# Schematic.net
KiCad netlist of a schematic drawn in Altium Designer
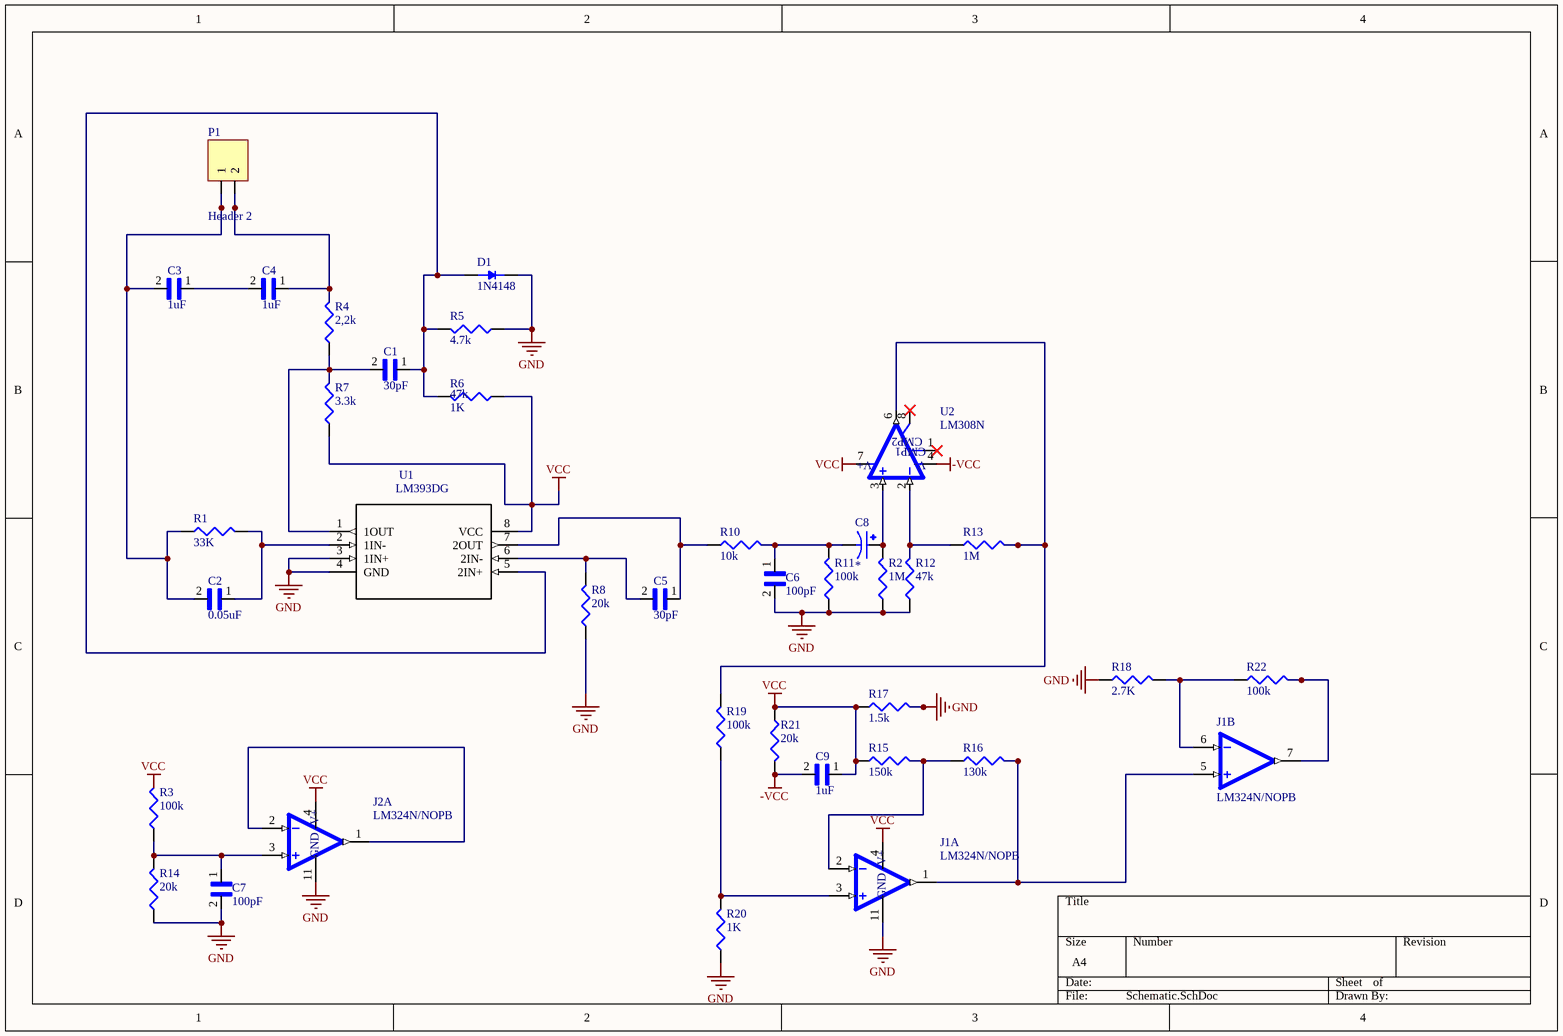
[diagram p0: Schematic.SchDoc]

(export (version "E")
  (design (tool "Eeschema 10.0.6"))
  (components
    (comp (ref "C1")
      (value "30pF")
      (footprint "CAPC3216X190")
      (description "ÐšÐµÑ€Ð°Ð¼Ð¸Ñ‡ÐµÑÐºÐ¸Ð¹ ÐºÐ¾Ð½Ð´ÐµÐ½ÑÐ°Ñ‚Ð¾Ñ€")
      (fields (field (name "MP") "GRM31CC80E157ME11K") (field (name "MF") "Murata"))
      (libsource (lib "GRM31CC80E157ME11K") (part "GRM31CC80E157ME11K"))
    )
    (comp (ref "C2")
      (value "0.05uF")
      (footprint "CAPC3216X190")
      (description "ÐšÐµÑ€Ð°Ð¼Ð¸Ñ‡ÐµÑÐºÐ¸Ð¹ ÐºÐ¾Ð½Ð´ÐµÐ½ÑÐ°Ñ‚Ð¾Ñ€")
      (fields (field (name "MP") "GRM31CC80E157ME11K") (field (name "MF") "Murata"))
      (libsource (lib "GRM31CC80E157ME11K") (part "GRM31CC80E157ME11K"))
    )
    (comp (ref "C3")
      (value "1uF")
      (footprint "CAPC3216X190")
      (description "ÐšÐµÑ€Ð°Ð¼Ð¸Ñ‡ÐµÑÐºÐ¸Ð¹ ÐºÐ¾Ð½Ð´ÐµÐ½ÑÐ°Ñ‚Ð¾Ñ€")
      (fields (field (name "MP") "GRM31CC80E157ME11K") (field (name "MF") "Murata"))
      (libsource (lib "GRM31CC80E157ME11K") (part "GRM31CC80E157ME11K"))
    )
    (comp (ref "C4")
      (value "1uF")
      (footprint "CAPC3216X190")
      (description "ÐšÐµÑ€Ð°Ð¼Ð¸Ñ‡ÐµÑÐºÐ¸Ð¹ ÐºÐ¾Ð½Ð´ÐµÐ½ÑÐ°Ñ‚Ð¾Ñ€")
      (fields (field (name "MP") "GRM31CC80E157ME11K") (field (name "MF") "Murata"))
      (libsource (lib "GRM31CC80E157ME11K") (part "GRM31CC80E157ME11K"))
    )
    (comp (ref "C5")
      (value "30pF")
      (footprint "CAPC3216X190")
      (description "ÐšÐµÑ€Ð°Ð¼Ð¸Ñ‡ÐµÑÐºÐ¸Ð¹ ÐºÐ¾Ð½Ð´ÐµÐ½ÑÐ°Ñ‚Ð¾Ñ€")
      (fields (field (name "MP") "GRM31CC80E157ME11K") (field (name "MF") "Murata"))
      (libsource (lib "GRM31CC80E157ME11K") (part "GRM31CC80E157ME11K"))
    )
    (comp (ref "C6")
      (value "100pF")
      (footprint "CAPC3216X190")
      (description "ÐšÐµÑ€Ð°Ð¼Ð¸Ñ‡ÐµÑÐºÐ¸Ð¹ ÐºÐ¾Ð½Ð´ÐµÐ½ÑÐ°Ñ‚Ð¾Ñ€")
      (fields (field (name "MP") "GRM31CC80E157ME11K") (field (name "MF") "Murata"))
      (libsource (lib "") (part "GRM31CC80E157ME11K_1"))
    )
    (comp (ref "C7")
      (value "100pF")
      (footprint "CAPC3216X190")
      (description "ÐšÐµÑ€Ð°Ð¼Ð¸Ñ‡ÐµÑÐºÐ¸Ð¹ ÐºÐ¾Ð½Ð´ÐµÐ½ÑÐ°Ñ‚Ð¾Ñ€")
      (fields (field (name "MP") "GRM31CC80E157ME11K") (field (name "MF") "Murata"))
      (libsource (lib "") (part "GRM31CC80E157ME11K_1"))
    )
    (comp (ref "C8")
      (value "*")
      (footprint "CAPPRD250W50D630H1120")
      (description "CAP ALUM 33UF 20% 63V RADIAL")
      (fields (field (name "MF") "Panasonic") (field (name "MP") "ECA1JM330I"))
      (libsource (lib "ECA1JM330I") (part "ECA1JM330I"))
    )
    (comp (ref "C9")
      (value "1uF")
      (footprint "CAPC3216X190")
      (description "ÐšÐµÑ€Ð°Ð¼Ð¸Ñ‡ÐµÑÐºÐ¸Ð¹ ÐºÐ¾Ð½Ð´ÐµÐ½ÑÐ°Ñ‚Ð¾Ñ€")
      (fields (field (name "MP") "GRM31CC80E157ME11K") (field (name "MF") "Murata"))
      (libsource (lib "GRM31CC80E157ME11K") (part "GRM31CC80E157ME11K"))
    )
    (comp (ref "D1")
      (value "1N4148")
      (footprint "DIODFN60X30X36-2N")
      (description "Diode Schottky 30V 100mA Surface Mount GMD2")
      (fields (field (name "MP") "RB520ZS-30T2R") (field (name "MF") "Rohm"))
      (libsource (lib "RB520ZS-30T2R") (part "RB520ZS-30T2R"))
    )
    (comp (ref "J1")
      (value "LM324N/NOPB")
      (footprint "DIP825W47P254L1917H533Q14")
      (description "Quad, 30-V, 1.2-MHz operational amplifier")
      (fields (field (name "MP") "LM324N") (field (name "MF") "Texas Instruments"))
      (libsource (lib "LM324N_NOPB") (part "LM324N/NOPB"))
    )
    (comp (ref "J2")
      (value "LM324N/NOPB")
      (footprint "DIP825W47P254L1917H533Q14")
      (description "Quad, 30-V, 1.2-MHz operational amplifier")
      (fields (field (name "MP") "LM324N") (field (name "MF") "Texas Instruments"))
      (libsource (lib "LM324N_NOPB") (part "LM324N/NOPB"))
    )
    (comp (ref "P1")
      (value "Header 2")
      (footprint "HDR1X2")
      (description "Header, 2-Pin")
      (fields (field (name "PUBLISHER") "Altium Limited"))
      (libsource (lib "Miscellaneous Connectors") (part "Header 2"))
    )
    (comp (ref "R1")
      (value "33K")
      (footprint "J1-0603")
      (description "Resistor")
      (fields (field (name "PUBLISHER") "Altium Limited"))
      (libsource (lib "Miscellaneous Devices") (part "Res3"))
    )
    (comp (ref "R2")
      (value "1M")
      (footprint "J1-0603")
      (description "Resistor")
      (fields (field (name "PUBLISHER") "Altium Limited"))
      (libsource (lib "Miscellaneous Devices") (part "Res3"))
    )
    (comp (ref "R3")
      (value "100k")
      (footprint "J1-0603")
      (description "Resistor")
      (fields (field (name "PUBLISHER") "Altium Limited"))
      (libsource (lib "Miscellaneous Devices") (part "Res3"))
    )
    (comp (ref "R4")
      (value "2,2k")
      (footprint "J1-0603")
      (description "Resistor")
      (fields (field (name "PUBLISHER") "Altium Limited"))
      (libsource (lib "Miscellaneous Devices") (part "Res3"))
    )
    (comp (ref "R5")
      (value "4.7k")
      (footprint "J1-0603")
      (description "Resistor")
      (fields (field (name "PUBLISHER") "Altium Limited"))
      (libsource (lib "Miscellaneous Devices") (part "Res3"))
    )
    (comp (ref "R6")
      (value "47k")
      (footprint "J1-0603")
      (description "Resistor")
      (fields (field (name "ALTIUM_VALUE") "1K") (field (name "PUBLISHER") "Altium Limited"))
      (libsource (lib "Miscellaneous Devices") (part "Res3"))
    )
    (comp (ref "R7")
      (value "3.3k")
      (footprint "J1-0603")
      (description "Resistor")
      (fields (field (name "PUBLISHER") "Altium Limited"))
      (libsource (lib "Miscellaneous Devices") (part "Res3"))
    )
    (comp (ref "R8")
      (value "20k")
      (footprint "J1-0603")
      (description "Resistor")
      (fields (field (name "PUBLISHER") "Altium Limited"))
      (libsource (lib "Miscellaneous Devices") (part "Res3"))
    )
    (comp (ref "R10")
      (value "10k")
      (footprint "J1-0603")
      (description "Resistor")
      (fields (field (name "PUBLISHER") "Altium Limited"))
      (libsource (lib "Miscellaneous Devices") (part "Res3"))
    )
    (comp (ref "R11")
      (value "100k")
      (footprint "J1-0603")
      (description "Resistor")
      (fields (field (name "PUBLISHER") "Altium Limited"))
      (libsource (lib "Miscellaneous Devices") (part "Res3"))
    )
    (comp (ref "R12")
      (value "47k")
      (footprint "J1-0603")
      (description "Resistor")
      (fields (field (name "PUBLISHER") "Altium Limited"))
      (libsource (lib "Miscellaneous Devices") (part "Res3"))
    )
    (comp (ref "R13")
      (value "1M")
      (footprint "J1-0603")
      (description "Resistor")
      (fields (field (name "PUBLISHER") "Altium Limited"))
      (libsource (lib "Miscellaneous Devices") (part "Res3"))
    )
    (comp (ref "R14")
      (value "20k")
      (footprint "J1-0603")
      (description "Resistor")
      (fields (field (name "PUBLISHER") "Altium Limited"))
      (libsource (lib "Miscellaneous Devices") (part "Res3"))
    )
    (comp (ref "R15")
      (value "150k")
      (footprint "J1-0603")
      (description "Resistor")
      (fields (field (name "PUBLISHER") "Altium Limited"))
      (libsource (lib "Miscellaneous Devices") (part "Res3"))
    )
    (comp (ref "R16")
      (value "130k")
      (footprint "J1-0603")
      (description "Resistor")
      (fields (field (name "PUBLISHER") "Altium Limited"))
      (libsource (lib "Miscellaneous Devices") (part "Res3"))
    )
    (comp (ref "R17")
      (value "1.5k")
      (footprint "J1-0603")
      (description "Resistor")
      (fields (field (name "PUBLISHER") "Altium Limited"))
      (libsource (lib "Miscellaneous Devices") (part "Res3"))
    )
    (comp (ref "R18")
      (value "2.7K")
      (footprint "J1-0603")
      (description "Resistor")
      (fields (field (name "PUBLISHER") "Altium Limited"))
      (libsource (lib "Miscellaneous Devices") (part "Res3"))
    )
    (comp (ref "R19")
      (value "100k")
      (footprint "J1-0603")
      (description "Resistor")
      (fields (field (name "PUBLISHER") "Altium Limited"))
      (libsource (lib "Miscellaneous Devices") (part "Res3"))
    )
    (comp (ref "R20")
      (value "1K")
      (footprint "J1-0603")
      (description "Resistor")
      (fields (field (name "PUBLISHER") "Altium Limited"))
      (libsource (lib "Miscellaneous Devices") (part "Res3"))
    )
    (comp (ref "R21")
      (value "20k")
      (footprint "J1-0603")
      (description "Resistor")
      (fields (field (name "PUBLISHER") "Altium Limited"))
      (libsource (lib "Miscellaneous Devices") (part "Res3"))
    )
    (comp (ref "R22")
      (value "100k")
      (footprint "J1-0603")
      (description "Resistor")
      (fields (field (name "PUBLISHER") "Altium Limited"))
      (libsource (lib "Miscellaneous Devices") (part "Res3"))
    )
    (comp (ref "U1")
      (value "LM393DG")
      (footprint "SOIC127P599X175-8N")
      (description "Comparator General Purpose CMOS, DTL, ECL, MOS, Open-Collector, TTL 8-SOIC")
      (fields (field (name "MF") "ON Semiconductor"))
      (libsource (lib "LM393DG") (part "LM393DG"))
    )
    (comp (ref "U2")
      (value "LM308N")
      (footprint "LM301AN:DIP794W45P254L1016H533Q8")
      (libsource (lib "LM308N") (part "LM308N"))
    )
  )
  (nets
    (net (code "1") (name "-VCC") (class "Default")
      (node (ref "C9") (pin "2") (pinfunction "2_2") (pintype "passive"))
      (node (ref "R21") (pin "2") (pinfunction "2_2") (pintype "passive"))
      (node (ref "U2") (pin "4") (pinfunction "V-_4") (pintype "power_in"))
    )
    (net (code "2") (name "GND") (class "Default")
      (node (ref "C6") (pin "2") (pinfunction "2_2") (pintype "passive"))
      (node (ref "C7") (pin "2") (pinfunction "2_2") (pintype "passive"))
      (node (ref "D1") (pin "C") (pinfunction "C_C") (pintype "passive"))
      (node (ref "J1") (pin "11") (pinfunction "GND_11") (pintype "power_in"))
      (node (ref "J2") (pin "11") (pinfunction "GND_11") (pintype "power_in"))
      (node (ref "R11") (pin "1") (pinfunction "1_1") (pintype "passive"))
      (node (ref "R12") (pin "1") (pinfunction "1_1") (pintype "passive"))
      (node (ref "R14") (pin "1") (pinfunction "1_1") (pintype "passive"))
      (node (ref "R17") (pin "2") (pinfunction "2_2") (pintype "passive"))
      (node (ref "R18") (pin "1") (pinfunction "1_1") (pintype "passive"))
      (node (ref "R2") (pin "1") (pinfunction "1_1") (pintype "passive"))
      (node (ref "R20") (pin "1") (pinfunction "1_1") (pintype "passive"))
      (node (ref "R5") (pin "1") (pinfunction "1_1") (pintype "passive"))
      (node (ref "R8") (pin "1") (pinfunction "1_1") (pintype "passive"))
      (node (ref "U1") (pin "3") (pinfunction "1IN+_3") (pintype "input"))
      (node (ref "U1") (pin "4") (pinfunction "GND_4") (pintype "power_in"))
    )
    (net (code "3") (name "Net-(C2-Pad2)") (class "Default")
      (node (ref "C2") (pin "2") (pinfunction "2_2") (pintype "passive"))
      (node (ref "C3") (pin "2") (pinfunction "2_2") (pintype "passive"))
      (node (ref "P1") (pin "1") (pinfunction "1_1") (pintype "passive"))
      (node (ref "R1") (pin "1") (pinfunction "1_1") (pintype "passive"))
    )
    (net (code "4") (name "Net-(C3-Pad1)") (class "Default")
      (node (ref "C3") (pin "1") (pinfunction "1_1") (pintype "passive"))
      (node (ref "C4") (pin "2") (pinfunction "2_2") (pintype "passive"))
    )
    (net (code "5") (name "Net-(C4-Pad1)") (class "Default")
      (node (ref "C4") (pin "1") (pinfunction "1_1") (pintype "passive"))
      (node (ref "P1") (pin "2") (pinfunction "2_2") (pintype "passive"))
      (node (ref "R4") (pin "2") (pinfunction "2_2") (pintype "passive"))
    )
    (net (code "6") (name "Net-(C6-Pad1)") (class "Default")
      (node (ref "C6") (pin "1") (pinfunction "1_1") (pintype "passive"))
      (node (ref "C8") (pin "N") (pinfunction "N_N") (pintype "passive"))
      (node (ref "R10") (pin "2") (pinfunction "2_2") (pintype "passive"))
      (node (ref "R11") (pin "2") (pinfunction "2_2") (pintype "passive"))
    )
    (net (code "7") (name "Net-(J1A-1IN+)") (class "Default")
      (node (ref "J1") (pin "3") (pinfunction "1IN+_3") (pintype "input"))
      (node (ref "R19") (pin "1") (pinfunction "1_1") (pintype "passive"))
      (node (ref "R20") (pin "2") (pinfunction "2_2") (pintype "passive"))
    )
    (net (code "8") (name "Net-(J1A-1IN-)") (class "Default")
      (node (ref "J1") (pin "2") (pinfunction "1IN-_2") (pintype "input"))
      (node (ref "R15") (pin "2") (pinfunction "2_2") (pintype "passive"))
      (node (ref "R16") (pin "1") (pinfunction "1_1") (pintype "passive"))
    )
    (net (code "9") (name "Net-(J1A-1OUT)") (class "Default")
      (node (ref "J1") (pin "1") (pinfunction "1OUT_1") (pintype "output"))
      (node (ref "J1") (pin "5") (pinfunction "2IN+_5") (pintype "input"))
      (node (ref "R16") (pin "2") (pinfunction "2_2") (pintype "passive"))
    )
    (net (code "10") (name "Net-(J1B-2IN-)") (class "Default")
      (node (ref "J1") (pin "6") (pinfunction "2IN-_6") (pintype "input"))
      (node (ref "R18") (pin "2") (pinfunction "2_2") (pintype "passive"))
      (node (ref "R22") (pin "1") (pinfunction "1_1") (pintype "passive"))
    )
    (net (code "11") (name "Net-(J1B-2OUT)") (class "Default")
      (node (ref "J1") (pin "7") (pinfunction "2OUT_7") (pintype "output"))
      (node (ref "R22") (pin "2") (pinfunction "2_2") (pintype "passive"))
    )
    (net (code "12") (name "Net-(J2A-1IN+)") (class "Default")
      (node (ref "C7") (pin "1") (pinfunction "1_1") (pintype "passive"))
      (node (ref "J2") (pin "3") (pinfunction "1IN+_3") (pintype "input"))
      (node (ref "R14") (pin "2") (pinfunction "2_2") (pintype "passive"))
      (node (ref "R3") (pin "1") (pinfunction "1_1") (pintype "passive"))
    )
    (net (code "13") (name "Net-(J2A-1IN-)") (class "Default")
      (node (ref "J2") (pin "1") (pinfunction "1OUT_1") (pintype "output"))
      (node (ref "J2") (pin "2") (pinfunction "1IN-_2") (pintype "input"))
    )
    (net (code "14") (name "Net-(U1-1IN-)") (class "Default")
      (node (ref "C2") (pin "1") (pinfunction "1_1") (pintype "passive"))
      (node (ref "R1") (pin "2") (pinfunction "2_2") (pintype "passive"))
      (node (ref "U1") (pin "2") (pinfunction "1IN-_2") (pintype "input"))
    )
    (net (code "15") (name "Net-(U1-1OUT)") (class "Default")
      (node (ref "C1") (pin "2") (pinfunction "2_2") (pintype "passive"))
      (node (ref "R4") (pin "1") (pinfunction "1_1") (pintype "passive"))
      (node (ref "R7") (pin "2") (pinfunction "2_2") (pintype "passive"))
      (node (ref "U1") (pin "1") (pinfunction "1OUT_1") (pintype "output"))
    )
    (net (code "16") (name "Net-(U1-2IN+)") (class "Default")
      (node (ref "C1") (pin "1") (pinfunction "1_1") (pintype "passive"))
      (node (ref "D1") (pin "A") (pinfunction "A_A") (pintype "passive"))
      (node (ref "R5") (pin "2") (pinfunction "2_2") (pintype "passive"))
      (node (ref "R6") (pin "2") (pinfunction "2_2") (pintype "passive"))
      (node (ref "U1") (pin "5") (pinfunction "2IN+_5") (pintype "input"))
    )
    (net (code "17") (name "Net-(U1-2IN-)") (class "Default")
      (node (ref "C5") (pin "2") (pinfunction "2_2") (pintype "passive"))
      (node (ref "R8") (pin "2") (pinfunction "2_2") (pintype "passive"))
      (node (ref "U1") (pin "6") (pinfunction "2IN-_6") (pintype "input"))
    )
    (net (code "18") (name "Net-(U1-2OUT)") (class "Default")
      (node (ref "C5") (pin "1") (pinfunction "1_1") (pintype "passive"))
      (node (ref "R10") (pin "1") (pinfunction "1_1") (pintype "passive"))
      (node (ref "U1") (pin "7") (pinfunction "2OUT_7") (pintype "output"))
    )
    (net (code "19") (name "Net-(U2-+IN)") (class "Default")
      (node (ref "C8") (pin "P") (pinfunction "P_P") (pintype "passive"))
      (node (ref "R2") (pin "2") (pinfunction "2_2") (pintype "passive"))
      (node (ref "U2") (pin "3") (pinfunction "+IN_3") (pintype "input"))
    )
    (net (code "20") (name "Net-(U2--IN)") (class "Default")
      (node (ref "R12") (pin "2") (pinfunction "2_2") (pintype "passive"))
      (node (ref "R13") (pin "1") (pinfunction "1_1") (pintype "passive"))
      (node (ref "U2") (pin "2") (pinfunction "-IN_2") (pintype "input"))
    )
    (net (code "21") (name "Net-(U2-OUT)") (class "Default")
      (node (ref "R13") (pin "2") (pinfunction "2_2") (pintype "passive"))
      (node (ref "R19") (pin "2") (pinfunction "2_2") (pintype "passive"))
      (node (ref "U2") (pin "6") (pinfunction "OUT_6") (pintype "output"))
    )
    (net (code "22") (name "VCC") (class "Default")
      (node (ref "C9") (pin "1") (pinfunction "1_1") (pintype "passive"))
      (node (ref "J1") (pin "4") (pinfunction "V+_4") (pintype "power_in"))
      (node (ref "J2") (pin "4") (pinfunction "V+_4") (pintype "power_in"))
      (node (ref "R15") (pin "1") (pinfunction "1_1") (pintype "passive"))
      (node (ref "R17") (pin "1") (pinfunction "1_1") (pintype "passive"))
      (node (ref "R21") (pin "1") (pinfunction "1_1") (pintype "passive"))
      (node (ref "R6") (pin "1") (pinfunction "1_1") (pintype "passive"))
      (node (ref "R7") (pin "1") (pinfunction "1_1") (pintype "passive"))
      (node (ref "U1") (pin "8") (pinfunction "VCC_8") (pintype "power_in"))
      (node (ref "U2") (pin "7") (pinfunction "V+_7") (pintype "power_in"))
    )
    (net (code "23") (name "unconnected-(R3-Pad2)") (class "Default")
      (node (ref "R3") (pin "2") (pinfunction "2_2") (pintype "passive"))
    )
    (net (code "24") (name "unconnected-(U2-CMP1-Pad1)") (class "Default")
      (node (ref "U2") (pin "1") (pinfunction "CMP1_1") (pintype "passive+no_connect"))
    )
    (net (code "25") (name "unconnected-(U2-CMP2-Pad8)") (class "Default")
      (node (ref "U2") (pin "8") (pinfunction "CMP2_8") (pintype "passive+no_connect"))
    )
  )
)
